# MCISO-S03-V00-CAN_MAIN.net
KiCad netlist of a schematic drawn in Altium Designer
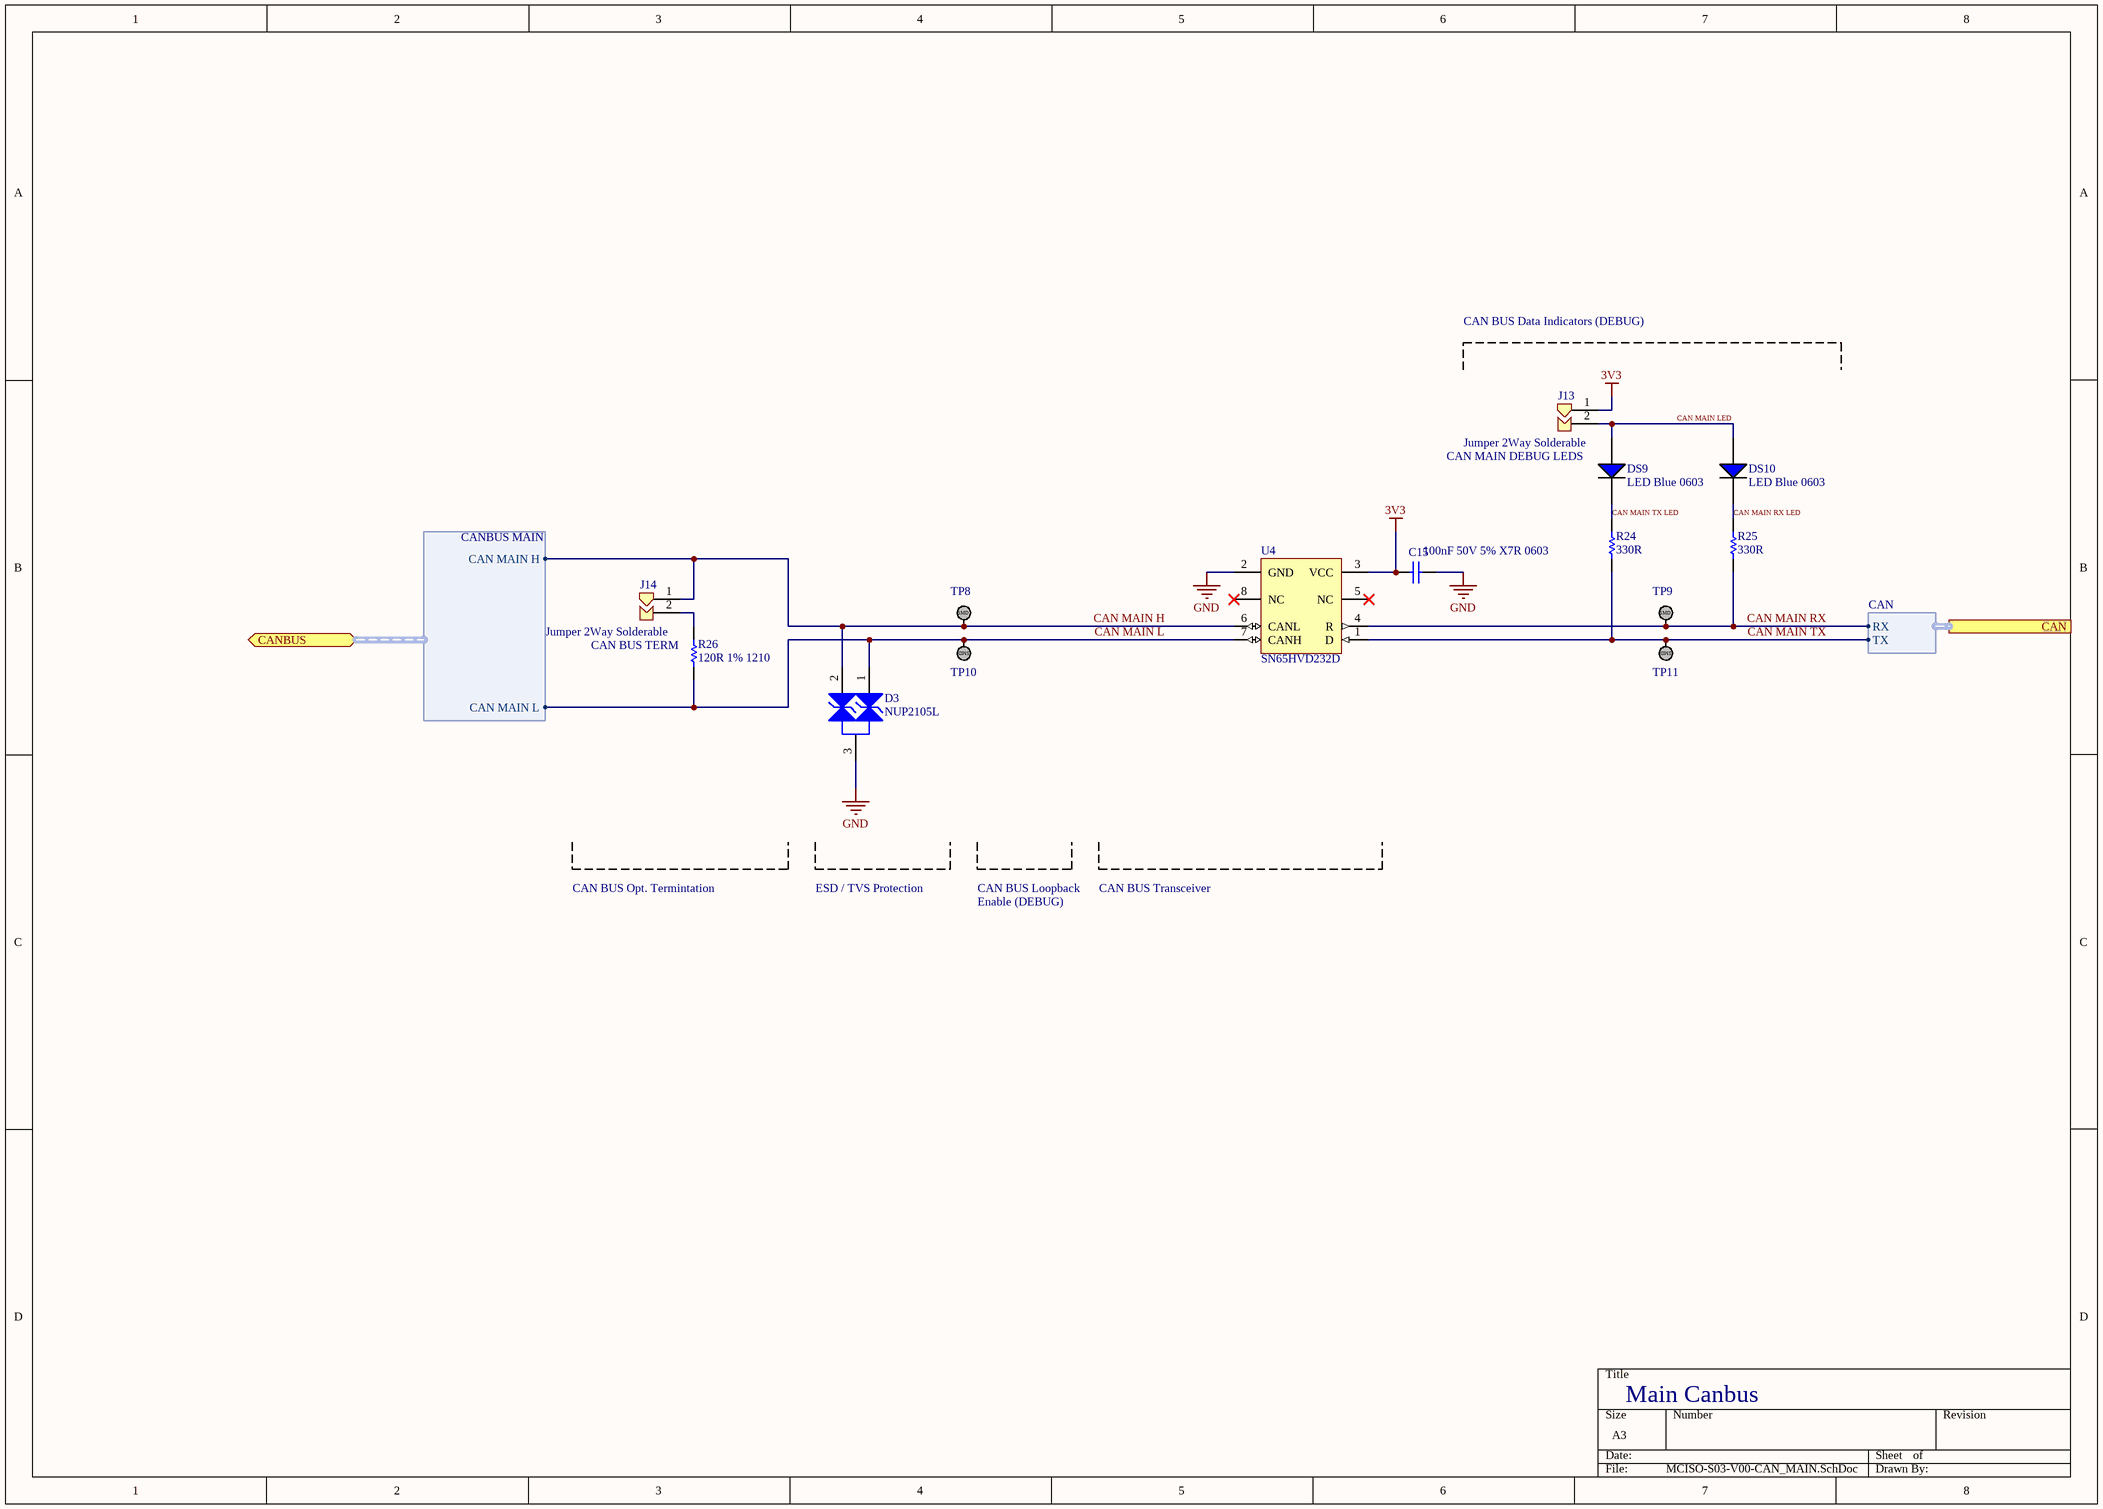
[diagram p0: MCISO-S03-V00-CAN_MAIN.SchDoc]

(export (version "E")
  (design (tool "Eeschema 10.0.6"))
  (components
    (comp (ref "C15")
      (value "100nF 50V 5% X7R 0603")
      (footprint "Cap_Ceramic_0603")
      (description "Capacitor, Ceramic, SMD, 100nF, 50V, 5%, X7R, 0603")
      (libsource (lib "StandardCapacitors") (part "100nF 50V 5% X7R 0603"))
    )
    (comp (ref "D3")
      (value "NUP2105L")
      (footprint "NUP2105L")
      (libsource (lib "QUTMS_CANLibrary") (part "NUP2105L"))
    )
    (comp (ref "DS9")
      (value "LED Blue 0603")
      (footprint "LED BLUE 0603")
      (libsource (lib "QUTMS_LEDLibrary") (part "LED BLUE 0603"))
    )
    (comp (ref "DS10")
      (value "LED Blue 0603")
      (footprint "LED BLUE 0603")
      (libsource (lib "QUTMS_LEDLibrary") (part "LED BLUE 0603"))
    )
    (comp (ref "J13")
      (value "Jumper 2Way Solderable")
      (footprint "Jumper_2Way_Solderable")
      (description "Jumper 2Way Side Solderable")
      (libsource (lib "QUTMS_JumperLibrary") (part "Jumper 2Way Side Solderable"))
    )
    (comp (ref "J14")
      (value "Jumper 2Way Solderable")
      (footprint "Jumper_2Way_Solderable")
      (description "Jumper 2Way Side Solderable")
      (libsource (lib "QUTMS_JumperLibrary") (part "Jumper 2Way Side Solderable"))
    )
    (comp (ref "R24")
      (value "330R")
      (footprint "Res_ThinFilm_0603")
      (description "Resistor, SMD, 330R, 0.1W, 5%, 0603")
      (libsource (lib "StandardResistors") (part "330R 5% 0603"))
    )
    (comp (ref "R25")
      (value "330R")
      (footprint "Res_ThinFilm_0603")
      (description "Resistor, SMD, 330R, 0.1W, 5%, 0603")
      (libsource (lib "StandardResistors") (part "330R 5% 0603"))
    )
    (comp (ref "R26")
      (value "120R 1% 1210")
      (footprint "Res_ThinFilm_1210")
      (description "Resistor, SMD, 120R, 0.25W, 1%, 1210")
      (libsource (lib "StandardResistors") (part "120R 1% 1210"))
    )
    (comp (ref "TP8")
      (value "TestPoint_SMD")
      (footprint "TestPointSMD")
      (libsource (lib "StandardTest") (part "TestPoint_SMD"))
    )
    (comp (ref "TP9")
      (value "TestPoint_SMD")
      (footprint "TestPointSMD")
      (libsource (lib "StandardTest") (part "TestPoint_SMD"))
    )
    (comp (ref "TP10")
      (value "TestPoint_SMD")
      (footprint "TestPointSMD")
      (libsource (lib "StandardTest") (part "TestPoint_SMD"))
    )
    (comp (ref "TP11")
      (value "TestPoint_SMD")
      (footprint "TestPointSMD")
      (libsource (lib "StandardTest") (part "TestPoint_SMD"))
    )
    (comp (ref "U4")
      (value "SN65HVD232D")
      (footprint "D0008A_L")
      (description "3.3 V CAN Transceiver, 17 mA, -40 to 85 degC, 8-pin SOIC (D), Green (RoHS & no Sb/Br)")
      (fields (field (name "MANUFACTURER") "Texas Instruments"))
      (libsource (lib "Altium Content Vault") (part "TI-SN65HVD232-SOIC_D-8"))
    )
  )
  (nets
    (net (code "4") (name "/CAN MAIN H") (class "Default")
      (node (ref "D3") (pin "2") (pinfunction "2_2") (pintype "passive"))
      (node (ref "J14") (pin "1") (pinfunction "1_1") (pintype "passive"))
      (node (ref "TP8") (pin "1") (pinfunction "1_1") (pintype "passive"))
      (node (ref "U4") (pin "6") (pinfunction "CANL_6") (pintype "bidirectional"))
    )
    (net (code "5") (name "/CAN MAIN L") (class "Default")
      (node (ref "D3") (pin "1") (pinfunction "1_1") (pintype "passive"))
      (node (ref "R26") (pin "1") (pinfunction "1_1") (pintype "passive"))
      (node (ref "TP10") (pin "1") (pinfunction "1_1") (pintype "passive"))
      (node (ref "U4") (pin "7") (pinfunction "CANH_7") (pintype "bidirectional"))
    )
    (net (code "6") (name "/CAN MAIN LED") (class "Default")
      (node (ref "DS10") (pin "1") (pinfunction "A_1") (pintype "passive"))
      (node (ref "DS9") (pin "1") (pinfunction "A_1") (pintype "passive"))
      (node (ref "J13") (pin "2") (pinfunction "2_2") (pintype "passive"))
    )
    (net (code "7") (name "/CAN MAIN RX") (class "Default")
      (node (ref "R25") (pin "1") (pinfunction "1_1") (pintype "passive"))
      (node (ref "TP9") (pin "1") (pinfunction "1_1") (pintype "passive"))
      (node (ref "U4") (pin "4") (pinfunction "R_4") (pintype "output"))
    )
    (net (code "8") (name "/CAN MAIN RX LED") (class "Default")
      (node (ref "DS10") (pin "2") (pinfunction "C_2") (pintype "passive"))
      (node (ref "R25") (pin "2") (pinfunction "2_2") (pintype "passive"))
    )
    (net (code "9") (name "/CAN MAIN TX") (class "Default")
      (node (ref "R24") (pin "1") (pinfunction "1_1") (pintype "passive"))
      (node (ref "TP11") (pin "1") (pinfunction "1_1") (pintype "passive"))
      (node (ref "U4") (pin "1") (pinfunction "D_1") (pintype "input"))
    )
    (net (code "10") (name "/CAN MAIN TX LED") (class "Default")
      (node (ref "DS9") (pin "2") (pinfunction "C_2") (pintype "passive"))
      (node (ref "R24") (pin "2") (pinfunction "2_2") (pintype "passive"))
    )
    (net (code "13") (name "3V3") (class "Default")
      (node (ref "C15") (pin "1") (pinfunction "1_1") (pintype "passive"))
      (node (ref "J13") (pin "1") (pinfunction "1_1") (pintype "passive"))
      (node (ref "U4") (pin "3") (pinfunction "VCC_3") (pintype "power_in"))
    )
    (net (code "14") (name "GND") (class "Default")
      (node (ref "C15") (pin "2") (pinfunction "2_2") (pintype "passive"))
      (node (ref "D3") (pin "3") (pinfunction "3_3") (pintype "passive"))
      (node (ref "U4") (pin "2") (pinfunction "GND_2") (pintype "power_in"))
    )
    (net (code "15") (name "Net-(J14-Pad2)") (class "Default")
      (node (ref "J14") (pin "2") (pinfunction "2_2") (pintype "passive"))
      (node (ref "R26") (pin "2") (pinfunction "2_2") (pintype "passive"))
    )
    (net (code "16") (name "unconnected-(U4-NC-Pad5)") (class "Default")
      (node (ref "U4") (pin "5") (pinfunction "NC_5") (pintype "passive+no_connect"))
    )
    (net (code "17") (name "unconnected-(U4-NC-Pad8)") (class "Default")
      (node (ref "U4") (pin "8") (pinfunction "NC_8") (pintype "passive+no_connect"))
    )
  )
)
